# Anemoia-ESP32.net
KiCad netlist of a schematic drawn in Altium Designer
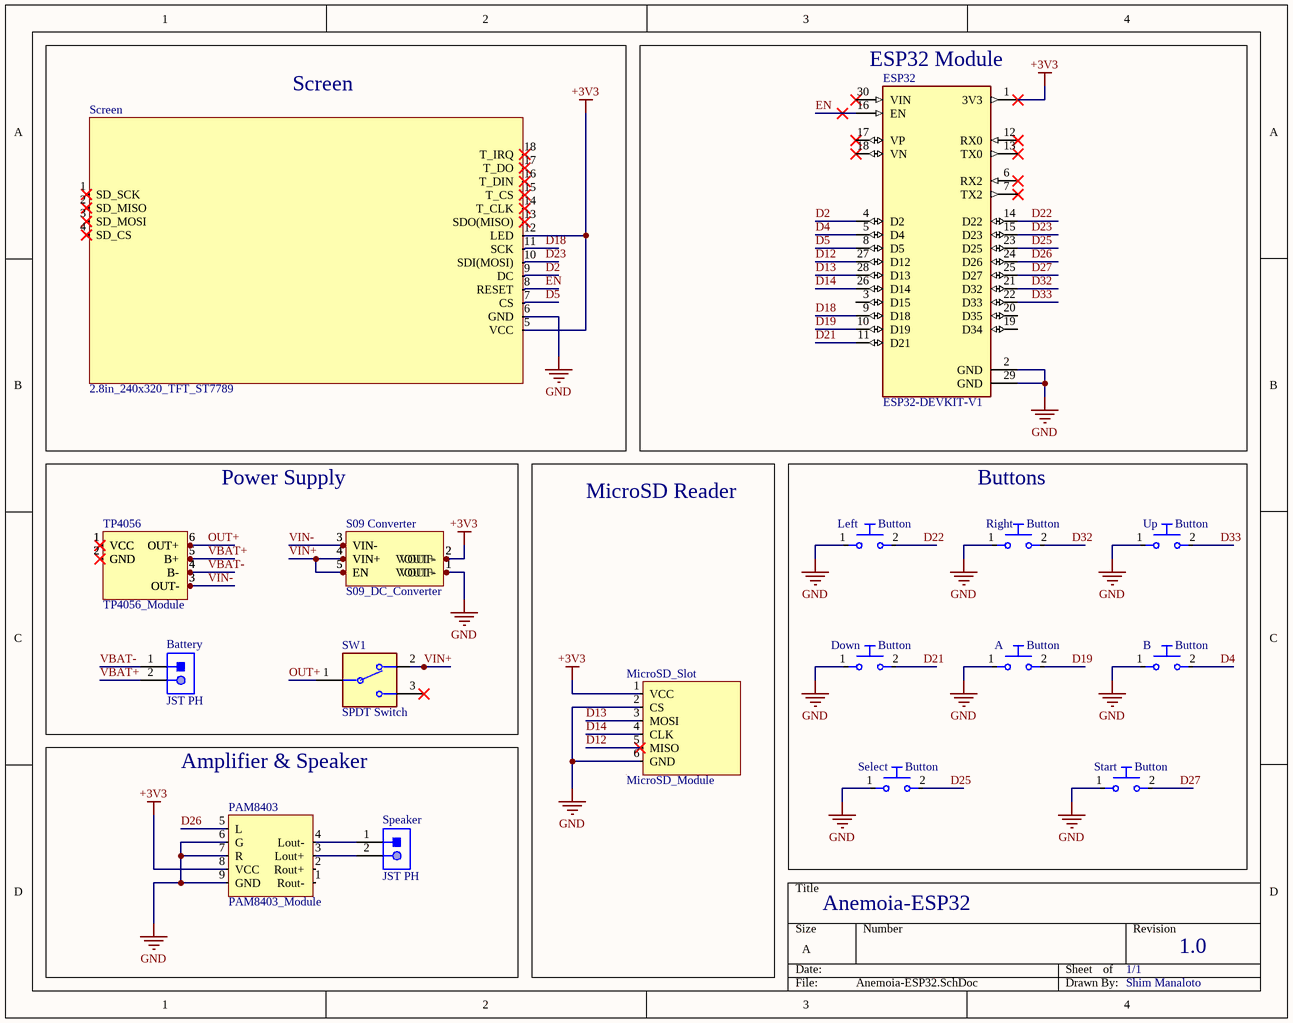
[diagram p0: Anemoia-ESP32.SchDoc]

(export (version "E")
  (design (tool "Eeschema 10.0.6"))
  (components
    (comp (ref "A")
      (value "Button")
      (footprint "12x12x7.3mm_Tactile_Push_Button")
      (libsource (lib "MicroSD_Module") (part "12x12x7.3mm_Tactile_Push_Button"))
    )
    (comp (ref "B")
      (value "Button")
      (footprint "12x12x7.3mm_Tactile_Push_Button")
      (libsource (lib "MicroSD_Module") (part "12x12x7.3mm_Tactile_Push_Button"))
    )
    (comp (ref "Battery")
      (value "JST PH")
      (footprint "JST-S2B-PH-K-S_V")
      (description "CONN HEADER TH R/A 2POS 2mm")
      (fields
        (field (name "MANUFACTURER") "JST")
        (field (name "MANUFACTURER PART NUMBER") "S2B-PH-K-S(LF)(SN)")
      )
      (libsource (lib "Anemoia") (part "S2B-PH-K-S(LF)(SN)"))
    )
    (comp (ref "Down")
      (value "Button")
      (footprint "12x12x7.3mm_Tactile_Push_Button")
      (libsource (lib "MicroSD_Module") (part "12x12x7.3mm_Tactile_Push_Button"))
    )
    (comp (ref "ESP32")
      (value "ESP32-DEVKIT-V1")
      (footprint "MODULE_ESP32_DEVKIT_V1")
      (fields (field (name "MF") "Do it"))
      (libsource (lib "ESP32-DEVKIT-V1") (part "ESP32-DEVKIT-V1"))
    )
    (comp (ref "Left")
      (value "Button")
      (footprint "12x12x7.3mm_Tactile_Push_Button")
      (libsource (lib "MicroSD_Module") (part "12x12x7.3mm_Tactile_Push_Button"))
    )
    (comp (ref "MicroSD_Slot")
      (value "MicroSD_Module")
      (footprint "MicroSD_Module")
      (description "3.3V MicroSD Module")
      (libsource (lib "MicroSD_Module") (part "MicroSD_Module"))
    )
    (comp (ref "PAM8403")
      (value "PAM8403_Module")
      (footprint "PAM8403")
      (libsource (lib "MicroSD_Module") (part "PAM8403_Module"))
    )
    (comp (ref "Right")
      (value "Button")
      (footprint "12x12x7.3mm_Tactile_Push_Button")
      (libsource (lib "MicroSD_Module") (part "12x12x7.3mm_Tactile_Push_Button"))
    )
    (comp (ref "S09 Converter")
      (value "S09_DC_Converter")
      (footprint "S09_DC_Converter")
      (libsource (lib "Anemoia") (part "S09_DC_Converter"))
    )
    (comp (ref "Screen")
      (value "2.8in_240x320_TFT_ST7789")
      (footprint "2.8in_240x320_TFT_ST7789")
      (libsource (lib "MicroSD_Module") (part "2.8in_240x320_TFT_ST7789"))
    )
    (comp (ref "Select")
      (value "Button")
      (footprint "12x12x7.3mm_Tactile_Push_Button")
      (libsource (lib "MicroSD_Module") (part "12x12x7.3mm_Tactile_Push_Button"))
    )
    (comp (ref "Speaker")
      (value "JST PH")
      (footprint "JST-S2B-PH-K-S_V")
      (description "CONN HEADER TH R/A 2POS 2mm")
      (fields
        (field (name "MANUFACTURER") "JST")
        (field (name "MANUFACTURER PART NUMBER") "S2B-PH-K-S(LF)(SN)")
      )
      (libsource (lib "Anemoia") (part "S2B-PH-K-S(LF)(SN)"))
    )
    (comp (ref "Start")
      (value "Button")
      (footprint "12x12x7.3mm_Tactile_Push_Button")
      (libsource (lib "MicroSD_Module") (part "12x12x7.3mm_Tactile_Push_Button"))
    )
    (comp (ref "SW1")
      (value "SPDT Switch")
      (footprint "SPDT_Switch")
      (libsource (lib "Anemoia") (part "SPDT Switch"))
    )
    (comp (ref "TP4056")
      (value "TP4056_Module")
      (footprint "TP4056_Module")
      (libsource (lib "MicroSD_Module") (part "TP4056_Module"))
    )
    (comp (ref "Up")
      (value "Button")
      (footprint "12x12x7.3mm_Tactile_Push_Button")
      (libsource (lib "MicroSD_Module") (part "12x12x7.3mm_Tactile_Push_Button"))
    )
  )
  (nets
    (net (code "1") (name "+3V3") (class "Default")
      (node (ref "ESP32") (pin "1") (pinfunction "3V3_1") (pintype "output"))
      (node (ref "MicroSD_Slot") (pin "1") (pinfunction "VCC_1") (pintype "power_in"))
      (node (ref "PAM8403") (pin "8") (pinfunction "VCC_8") (pintype "power_in"))
      (node (ref "S09 Converter") (pin "2") (pinfunction "VOUT-_2") (pintype "power_in"))
      (node (ref "Screen") (pin "12") (pinfunction "LED_12") (pintype "power_in"))
      (node (ref "Screen") (pin "5") (pinfunction "VCC_5") (pintype "power_in"))
    )
    (net (code "2") (name "/D2") (class "Default")
      (node (ref "ESP32") (pin "4") (pinfunction "D2_4") (pintype "bidirectional"))
      (node (ref "Screen") (pin "9") (pinfunction "DC_9") (pintype "input"))
    )
    (net (code "3") (name "/D4") (class "Default")
      (node (ref "B") (pin "2") (pintype "passive"))
      (node (ref "ESP32") (pin "5") (pinfunction "D4_5") (pintype "bidirectional"))
    )
    (net (code "4") (name "/D5") (class "Default")
      (node (ref "ESP32") (pin "8") (pinfunction "D5_8") (pintype "bidirectional"))
      (node (ref "Screen") (pin "7") (pinfunction "CS_7") (pintype "input"))
    )
    (net (code "5") (name "/D12") (class "Default")
      (node (ref "ESP32") (pin "27") (pinfunction "D12_27") (pintype "bidirectional"))
      (node (ref "MicroSD_Slot") (pin "5") (pinfunction "MISO_5") (pintype "output"))
    )
    (net (code "6") (name "/D13") (class "Default")
      (node (ref "ESP32") (pin "28") (pinfunction "D13_28") (pintype "bidirectional"))
      (node (ref "MicroSD_Slot") (pin "3") (pinfunction "MOSI_3") (pintype "input"))
    )
    (net (code "7") (name "/D14") (class "Default")
      (node (ref "ESP32") (pin "26") (pinfunction "D14_26") (pintype "bidirectional"))
      (node (ref "MicroSD_Slot") (pin "4") (pinfunction "CLK_4") (pintype "input"))
    )
    (net (code "8") (name "/D18") (class "Default")
      (node (ref "ESP32") (pin "9") (pinfunction "D18_9") (pintype "bidirectional"))
      (node (ref "Screen") (pin "11") (pinfunction "SCK_11") (pintype "input"))
    )
    (net (code "9") (name "/D19") (class "Default")
      (node (ref "A") (pin "2") (pintype "passive"))
      (node (ref "ESP32") (pin "10") (pinfunction "D19_10") (pintype "bidirectional"))
    )
    (net (code "10") (name "/D21") (class "Default")
      (node (ref "Down") (pin "2") (pintype "passive"))
      (node (ref "ESP32") (pin "11") (pinfunction "D21_11") (pintype "bidirectional"))
    )
    (net (code "11") (name "/D22") (class "Default")
      (node (ref "ESP32") (pin "14") (pinfunction "D22_14") (pintype "bidirectional"))
      (node (ref "Left") (pin "2") (pintype "passive"))
    )
    (net (code "12") (name "/D23") (class "Default")
      (node (ref "ESP32") (pin "15") (pinfunction "D23_15") (pintype "bidirectional"))
      (node (ref "Screen") (pin "10") (pinfunction "SDI(MOSI)_10") (pintype "input"))
    )
    (net (code "13") (name "/D25") (class "Default")
      (node (ref "ESP32") (pin "23") (pinfunction "D25_23") (pintype "bidirectional"))
      (node (ref "Select") (pin "2") (pintype "passive"))
    )
    (net (code "14") (name "/D26") (class "Default")
      (node (ref "ESP32") (pin "24") (pinfunction "D26_24") (pintype "bidirectional"))
      (node (ref "PAM8403") (pin "5") (pinfunction "L_5") (pintype "input"))
    )
    (net (code "15") (name "/D27") (class "Default")
      (node (ref "ESP32") (pin "25") (pinfunction "D27_25") (pintype "bidirectional"))
      (node (ref "Start") (pin "2") (pintype "passive"))
    )
    (net (code "16") (name "/D32") (class "Default")
      (node (ref "ESP32") (pin "21") (pinfunction "D32_21") (pintype "bidirectional"))
      (node (ref "Right") (pin "2") (pintype "passive"))
    )
    (net (code "17") (name "/D33") (class "Default")
      (node (ref "ESP32") (pin "22") (pinfunction "D33_22") (pintype "bidirectional"))
      (node (ref "Up") (pin "2") (pintype "passive"))
    )
    (net (code "18") (name "/EN") (class "Default")
      (node (ref "ESP32") (pin "16") (pinfunction "EN_16") (pintype "input"))
      (node (ref "Screen") (pin "8") (pinfunction "RESET_8") (pintype "input"))
    )
    (net (code "19") (name "/OUT+") (class "Default")
      (node (ref "SW1") (pin "1") (pinfunction "1_1") (pintype "passive"))
      (node (ref "TP4056") (pin "6") (pinfunction "OUT+_6") (pintype "power_in"))
    )
    (net (code "20") (name "/VBAT+") (class "Default")
      (node (ref "Battery") (pin "2") (pinfunction "2_2") (pintype "passive"))
      (node (ref "TP4056") (pin "5") (pinfunction "B+_5") (pintype "power_in"))
    )
    (net (code "21") (name "/VBAT-") (class "Default")
      (node (ref "Battery") (pin "1") (pinfunction "1_1") (pintype "passive"))
      (node (ref "TP4056") (pin "4") (pinfunction "B-_4") (pintype "power_in"))
    )
    (net (code "22") (name "/VIN+") (class "Default")
      (node (ref "S09 Converter") (pin "4") (pinfunction "VIN+_4") (pintype "power_in"))
      (node (ref "S09 Converter") (pin "5") (pinfunction "EN_5") (pintype "input"))
      (node (ref "SW1") (pin "2") (pinfunction "2_2") (pintype "passive"))
    )
    (net (code "23") (name "/VIN-") (class "Default")
      (node (ref "S09 Converter") (pin "3") (pinfunction "VIN-_3") (pintype "power_in"))
      (node (ref "TP4056") (pin "3") (pinfunction "OUT-_3") (pintype "power_in"))
    )
    (net (code "24") (name "GND") (class "Default")
      (node (ref "A") (pin "1") (pintype "passive"))
      (node (ref "B") (pin "1") (pintype "passive"))
      (node (ref "Down") (pin "1") (pintype "passive"))
      (node (ref "ESP32") (pin "2") (pinfunction "GND_2") (pintype "power_in"))
      (node (ref "ESP32") (pin "29") (pinfunction "GND_29") (pintype "power_in"))
      (node (ref "Left") (pin "1") (pintype "passive"))
      (node (ref "MicroSD_Slot") (pin "2") (pinfunction "CS_2") (pintype "input"))
      (node (ref "MicroSD_Slot") (pin "6") (pinfunction "GND_6") (pintype "power_in"))
      (node (ref "PAM8403") (pin "6") (pinfunction "G_6") (pintype "power_in"))
      (node (ref "PAM8403") (pin "7") (pinfunction "R_7") (pintype "input"))
      (node (ref "PAM8403") (pin "9") (pinfunction "GND_9") (pintype "power_in"))
      (node (ref "Right") (pin "1") (pintype "passive"))
      (node (ref "S09 Converter") (pin "1") (pinfunction "VOUT-_1") (pintype "power_in"))
      (node (ref "Screen") (pin "6") (pinfunction "GND_6") (pintype "power_in"))
      (node (ref "Select") (pin "1") (pintype "passive"))
      (node (ref "Start") (pin "1") (pintype "passive"))
      (node (ref "Up") (pin "1") (pintype "passive"))
    )
    (net (code "25") (name "Net-(PAM8403-Lout+)") (class "Default")
      (node (ref "PAM8403") (pin "3") (pinfunction "Lout+_3") (pintype "output"))
      (node (ref "Speaker") (pin "2") (pinfunction "2_2") (pintype "passive"))
    )
    (net (code "26") (name "Net-(PAM8403-Lout-)") (class "Default")
      (node (ref "PAM8403") (pin "4") (pinfunction "Lout-_4") (pintype "output"))
      (node (ref "Speaker") (pin "1") (pinfunction "1_1") (pintype "passive"))
    )
    (net (code "27") (name "unconnected-(ESP32-D15-Pad3)") (class "Default")
      (node (ref "ESP32") (pin "3") (pinfunction "D15_3") (pintype "bidirectional"))
    )
    (net (code "28") (name "unconnected-(ESP32-D34-Pad19)") (class "Default")
      (node (ref "ESP32") (pin "19") (pinfunction "D34_19") (pintype "bidirectional"))
    )
    (net (code "29") (name "unconnected-(ESP32-D35-Pad20)") (class "Default")
      (node (ref "ESP32") (pin "20") (pinfunction "D35_20") (pintype "bidirectional"))
    )
    (net (code "30") (name "unconnected-(ESP32-RX0-Pad12)") (class "Default")
      (node (ref "ESP32") (pin "12") (pinfunction "RX0_12") (pintype "input+no_connect"))
    )
    (net (code "31") (name "unconnected-(ESP32-RX2-Pad6)") (class "Default")
      (node (ref "ESP32") (pin "6") (pinfunction "RX2_6") (pintype "input+no_connect"))
    )
    (net (code "32") (name "unconnected-(ESP32-TX0-Pad13)") (class "Default")
      (node (ref "ESP32") (pin "13") (pinfunction "TX0_13") (pintype "output+no_connect"))
    )
    (net (code "33") (name "unconnected-(ESP32-TX2-Pad7)") (class "Default")
      (node (ref "ESP32") (pin "7") (pinfunction "TX2_7") (pintype "output+no_connect"))
    )
    (net (code "34") (name "unconnected-(ESP32-VIN-Pad30)") (class "Default")
      (node (ref "ESP32") (pin "30") (pinfunction "VIN_30") (pintype "input+no_connect"))
    )
    (net (code "35") (name "unconnected-(ESP32-VN-Pad18)") (class "Default")
      (node (ref "ESP32") (pin "18") (pinfunction "VN_18") (pintype "bidirectional+no_connect"))
    )
    (net (code "36") (name "unconnected-(ESP32-VP-Pad17)") (class "Default")
      (node (ref "ESP32") (pin "17") (pinfunction "VP_17") (pintype "bidirectional+no_connect"))
    )
    (net (code "37") (name "unconnected-(PAM8403-Rout+-Pad2)") (class "Default")
      (node (ref "PAM8403") (pin "2") (pinfunction "Rout+_2") (pintype "output"))
    )
    (net (code "38") (name "unconnected-(PAM8403-Rout--Pad1)") (class "Default")
      (node (ref "PAM8403") (pin "1") (pinfunction "Rout-_1") (pintype "output"))
    )
    (net (code "39") (name "unconnected-(SW1-Pad3)") (class "Default")
      (node (ref "SW1") (pin "3") (pinfunction "3_3") (pintype "passive+no_connect"))
    )
    (net (code "40") (name "unconnected-(Screen-SDO(MISO)-Pad13)") (class "Default")
      (node (ref "Screen") (pin "13") (pinfunction "SDO(MISO)_13") (pintype "output+no_connect"))
    )
    (net (code "41") (name "unconnected-(Screen-SD_CS-Pad4)") (class "Default")
      (node (ref "Screen") (pin "4") (pinfunction "SD_CS_4") (pintype "input+no_connect"))
    )
    (net (code "42") (name "unconnected-(Screen-SD_MISO-Pad2)") (class "Default")
      (node (ref "Screen") (pin "2") (pinfunction "SD_MISO_2") (pintype "output+no_connect"))
    )
    (net (code "43") (name "unconnected-(Screen-SD_MOSI-Pad3)") (class "Default")
      (node (ref "Screen") (pin "3") (pinfunction "SD_MOSI_3") (pintype "input+no_connect"))
    )
    (net (code "44") (name "unconnected-(Screen-SD_SCK-Pad1)") (class "Default")
      (node (ref "Screen") (pin "1") (pinfunction "SD_SCK_1") (pintype "input+no_connect"))
    )
    (net (code "45") (name "unconnected-(Screen-T_CLK-Pad14)") (class "Default")
      (node (ref "Screen") (pin "14") (pinfunction "T_CLK_14") (pintype "input+no_connect"))
    )
    (net (code "46") (name "unconnected-(Screen-T_CS-Pad15)") (class "Default")
      (node (ref "Screen") (pin "15") (pinfunction "T_CS_15") (pintype "input+no_connect"))
    )
    (net (code "47") (name "unconnected-(Screen-T_DIN-Pad16)") (class "Default")
      (node (ref "Screen") (pin "16") (pinfunction "T_DIN_16") (pintype "input+no_connect"))
    )
    (net (code "48") (name "unconnected-(Screen-T_DO-Pad17)") (class "Default")
      (node (ref "Screen") (pin "17") (pinfunction "T_DO_17") (pintype "output+no_connect"))
    )
    (net (code "49") (name "unconnected-(Screen-T_IRQ-Pad18)") (class "Default")
      (node (ref "Screen") (pin "18") (pinfunction "T_IRQ_18") (pintype "output+no_connect"))
    )
    (net (code "50") (name "unconnected-(TP4056-GND-Pad2)") (class "Default")
      (node (ref "TP4056") (pin "2") (pinfunction "GND_2") (pintype "power_in+no_connect"))
    )
    (net (code "51") (name "unconnected-(TP4056-VCC-Pad1)") (class "Default")
      (node (ref "TP4056") (pin "1") (pinfunction "VCC_1") (pintype "power_in+no_connect"))
    )
  )
)
